# Qwiic_GPS.net
KiCad netlist of a schematic drawn in EAGLE
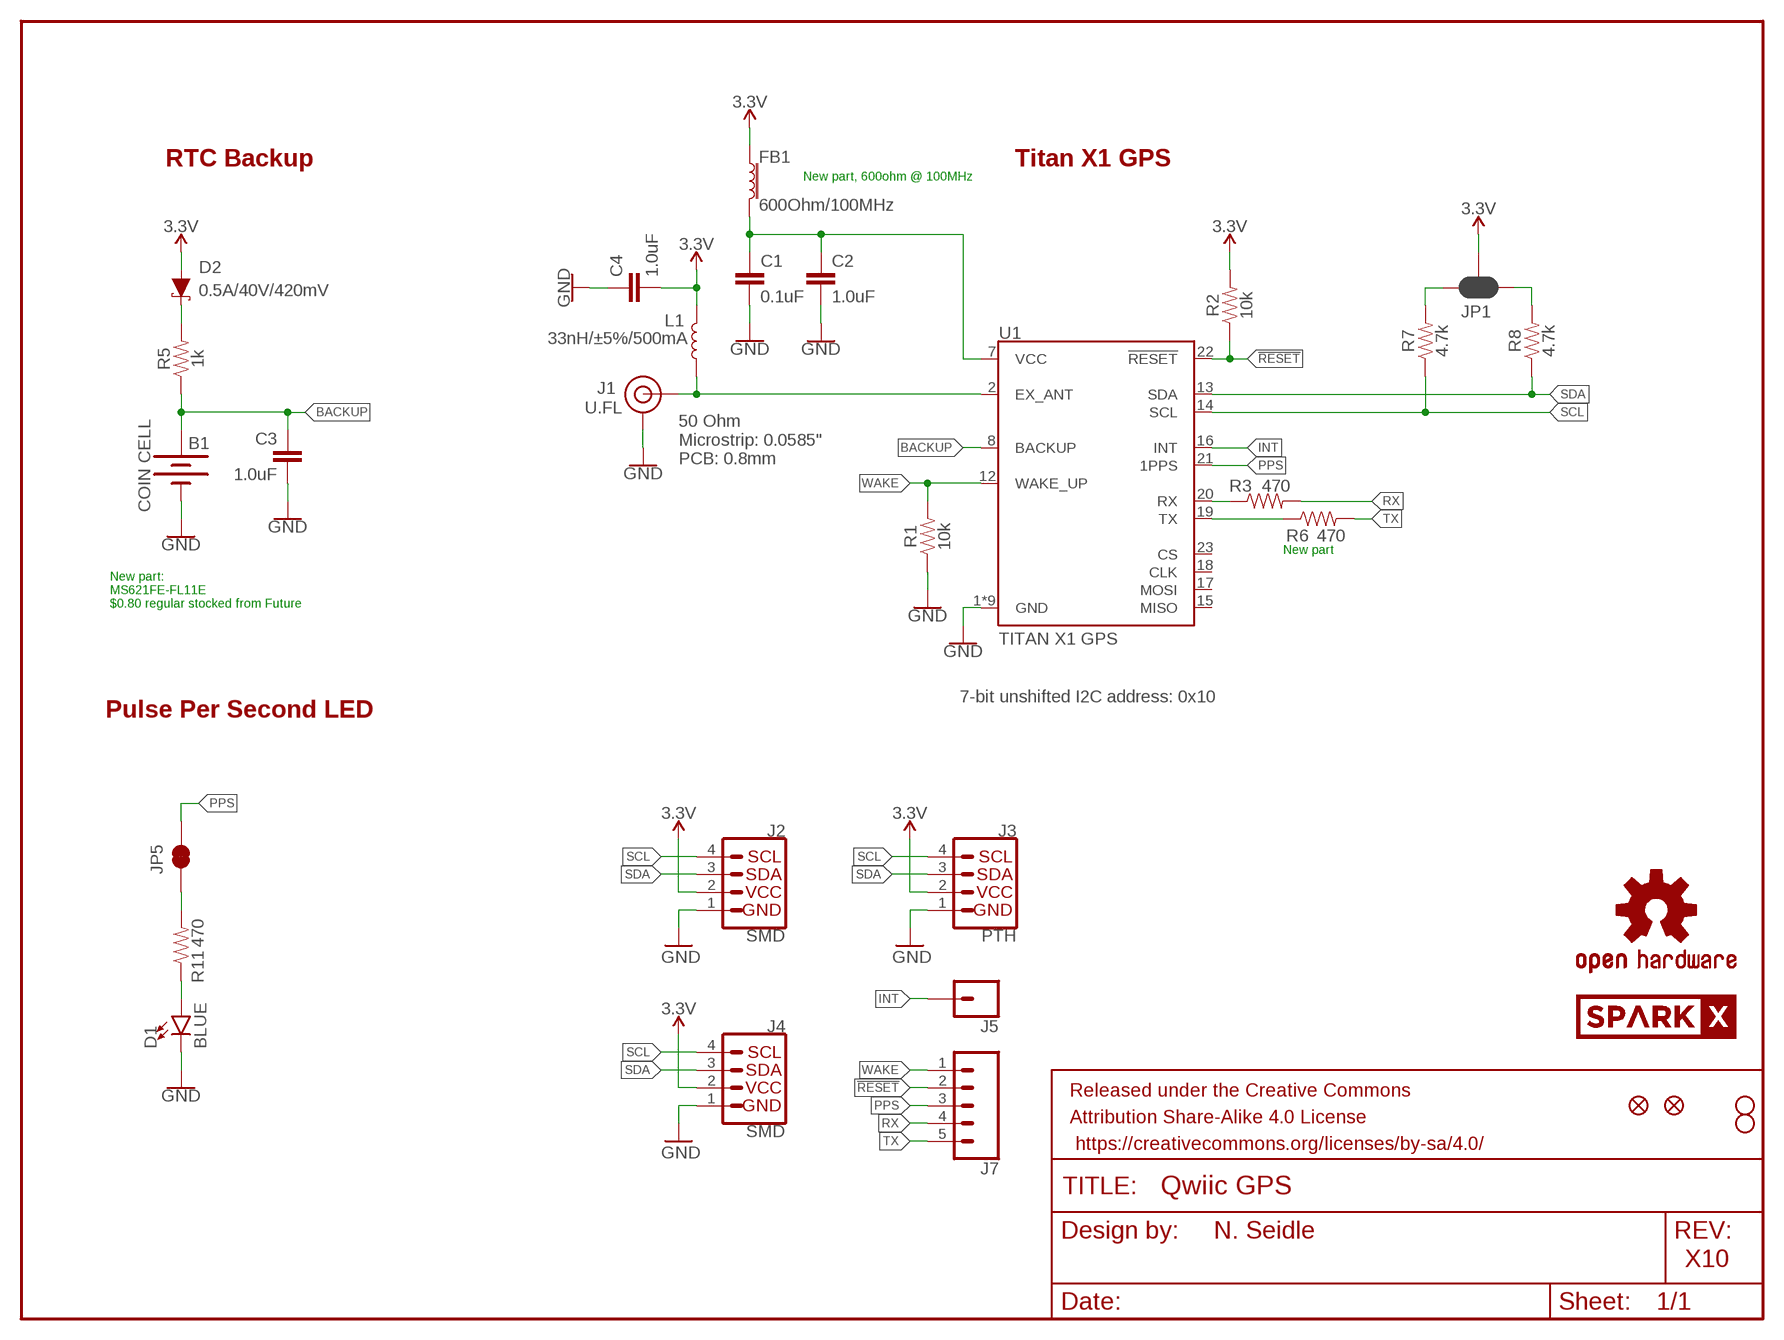
[diagram p0: schematic, sheet 1]

(export (version "E")
  (design (tool "Eeschema 10.0.6"))
  (components
    (comp (ref "B1")
      (value "COIN CELL")
      (footprint "eagle-import:6.8MM_COIN_CELL")
      (libsource (lib "eagle-import") (part "6.8MM_COIN_CELL"))
    )
    (comp (ref "C1")
      (value "0.1uF")
      (footprint "eagle-import:0603")
      (libsource (lib "eagle-import") (part "0.1UF-0603-25V-(+80/-20%)"))
    )
    (comp (ref "C2")
      (value "1.0uF")
      (footprint "eagle-import:0603")
      (libsource (lib "eagle-import") (part "1.0UF-0603-16V-10%"))
    )
    (comp (ref "C3")
      (value "1.0uF")
      (footprint "eagle-import:0603")
      (libsource (lib "eagle-import") (part "1.0UF-0603-16V-10%"))
    )
    (comp (ref "C4")
      (value "1.0uF")
      (footprint "eagle-import:0603")
      (libsource (lib "eagle-import") (part "1.0UF-0603-16V-10%"))
    )
    (comp (ref "D1")
      (value "BLUE")
      (footprint "eagle-import:LED-0603")
      (libsource (lib "eagle-import") (part "LED-BLUE0603"))
    )
    (comp (ref "D2")
      (value "0.5A/40V/420mV")
      (footprint "eagle-import:SOD-323")
      (libsource (lib "eagle-import") (part "DIODE-SCHOTTKY-PMEG4005EJ"))
    )
    (comp (ref "FB1")
      (value "600Ohm/100MHz")
      (footprint "eagle-import:0603")
      (libsource (lib "eagle-import") (part "FERRITE_BEAD-0603"))
    )
    (comp (ref "FRAME1")
      (value "FRAME-LETTER")
      (footprint "eagle-import:CREATIVE_COMMONS")
      (libsource (lib "eagle-import") (part "FRAME-LETTER"))
    )
    (comp (ref "J1")
      (value "U.FL")
      (footprint "eagle-import:U.FL")
      (libsource (lib "eagle-import") (part "U.FL"))
    )
    (comp (ref "J2")
      (value "SMD")
      (footprint "eagle-import:1X04_1MM_RA")
      (libsource (lib "eagle-import") (part "I2C_STANDARDJS-1MM"))
    )
    (comp (ref "J3")
      (value "PTH")
      (footprint "eagle-import:1X04_NO_SILK")
      (libsource (lib "eagle-import") (part "I2C_STANDARD_NO_SILK"))
    )
    (comp (ref "J4")
      (value "SMD")
      (footprint "eagle-import:1X04_1MM_RA")
      (libsource (lib "eagle-import") (part "I2C_STANDARDJS-1MM"))
    )
    (comp (ref "J5")
      (value "CONN_01PTH_NO_SILK_YES_STOP")
      (footprint "eagle-import:1X01_NO_SILK")
      (libsource (lib "eagle-import") (part "CONN_01PTH_NO_SILK_YES_STOP"))
    )
    (comp (ref "J7")
      (value "CONN_05NO_SILK")
      (footprint "eagle-import:1X05_NO_SILK")
      (libsource (lib "eagle-import") (part "CONN_05NO_SILK"))
    )
    (comp (ref "JP1")
      (value "JUMPER-SMT_3_2-NC_PASTE_SILK")
      (footprint "eagle-import:SMT-JUMPER_3_2-NC_PASTE_SILK")
      (libsource (lib "eagle-import") (part "JUMPER-SMT_3_2-NC_PASTE_SILK"))
    )
    (comp (ref "JP2")
      (value "FIDUCIALUFIDUCIAL")
      (footprint "eagle-import:MICRO-FIDUCIAL")
      (libsource (lib "eagle-import") (part "FIDUCIALUFIDUCIAL"))
    )
    (comp (ref "JP3")
      (value "STAND-OFF")
      (footprint "eagle-import:STAND-OFF")
      (libsource (lib "eagle-import") (part "STAND-OFF"))
    )
    (comp (ref "JP4")
      (value "STAND-OFF")
      (footprint "eagle-import:STAND-OFF")
      (libsource (lib "eagle-import") (part "STAND-OFF"))
    )
    (comp (ref "JP5")
      (value "JUMPER-SMT_2_NC_TRACE_NO-SILK")
      (footprint "eagle-import:SMT-JUMPER_2_NC_TRACE_NO-SILK")
      (libsource (lib "eagle-import") (part "JUMPER-SMT_2_NC_TRACE_NO-SILK"))
    )
    (comp (ref "JP6")
      (value "FIDUCIALUFIDUCIAL")
      (footprint "eagle-import:MICRO-FIDUCIAL")
      (libsource (lib "eagle-import") (part "FIDUCIALUFIDUCIAL"))
    )
    (comp (ref "L1")
      (value "33nH/±5%/500mA")
      (footprint "eagle-import:0603")
      (libsource (lib "eagle-import") (part "INDUCTOR-0603-33NH"))
    )
    (comp (ref "LOGO1")
      (value "OSHW-LOGOMINI")
      (footprint "eagle-import:OSHW-LOGO-MINI")
      (libsource (lib "eagle-import") (part "OSHW-LOGOMINI"))
    )
    (comp (ref "R1")
      (value "10k")
      (footprint "eagle-import:0603")
      (libsource (lib "eagle-import") (part "10KOHM-0603-1/10W-1%"))
    )
    (comp (ref "R2")
      (value "10k")
      (footprint "eagle-import:0603")
      (libsource (lib "eagle-import") (part "10KOHM-0603-1/10W-1%"))
    )
    (comp (ref "R3")
      (value "470")
      (footprint "eagle-import:0603")
      (libsource (lib "eagle-import") (part "470OHM-0603-1/10W-1%"))
    )
    (comp (ref "R5")
      (value "1k")
      (footprint "eagle-import:0603")
      (libsource (lib "eagle-import") (part "1KOHM-0603-1/10W-1%"))
    )
    (comp (ref "R6")
      (value "470")
      (footprint "eagle-import:0603")
      (libsource (lib "eagle-import") (part "470OHM-0603-1/10W-1%"))
    )
    (comp (ref "R7")
      (value "4.7k")
      (footprint "eagle-import:0603")
      (libsource (lib "eagle-import") (part "4.7KOHM-0603-1/10W-1%"))
    )
    (comp (ref "R8")
      (value "4.7k")
      (footprint "eagle-import:0603")
      (libsource (lib "eagle-import") (part "4.7KOHM-0603-1/10W-1%"))
    )
    (comp (ref "R11")
      (value "470")
      (footprint "eagle-import:0603")
      (libsource (lib "eagle-import") (part "470OHM-0603-1/10W-1%"))
    )
    (comp (ref "U$1")
      (value "SPARKX-LOGO5")
      (footprint "eagle-import:SPARKX-LARGE")
      (libsource (lib "eagle-import") (part "SPARKX-LOGO5"))
    )
    (comp (ref "U1")
      (value "TITAN X1 GPS")
      (footprint "eagle-import:TITAN_X1_GPS")
      (libsource (lib "eagle-import") (part "TITAN_X1_GPS"))
    )
  )
  (nets
    (net (code "1") (name "/~{RESET}") (class "Default")
      (node (ref "J7") (pin "2") (pinfunction "2_2") (pintype "passive"))
      (node (ref "R2") (pin "1") (pinfunction "1_1") (pintype "passive"))
      (node (ref "U1") (pin "22") (pinfunction "~{RESET}_22") (pintype "bidirectional"))
    )
    (net (code "2") (name "3.3V") (class "Default")
      (node (ref "C4") (pin "2") (pinfunction "2_2") (pintype "passive"))
      (node (ref "D2") (pin "A") (pinfunction "A_A") (pintype "passive"))
      (node (ref "FB1") (pin "1") (pinfunction "1_1") (pintype "passive"))
      (node (ref "J2") (pin "2") (pinfunction "VCC_2") (pintype "power_in"))
      (node (ref "J3") (pin "2") (pinfunction "VCC_2") (pintype "power_in"))
      (node (ref "J4") (pin "2") (pinfunction "VCC_2") (pintype "power_in"))
      (node (ref "JP1") (pin "2") (pinfunction "2_2") (pintype "passive"))
      (node (ref "L1") (pin "2") (pinfunction "2_2") (pintype "passive"))
      (node (ref "R2") (pin "2") (pinfunction "2_2") (pintype "passive"))
    )
    (net (code "3") (name "BACKUP") (class "Default")
      (node (ref "B1") (pin "+") (pinfunction "+_+") (pintype "power_in"))
      (node (ref "C3") (pin "1") (pinfunction "1_1") (pintype "passive"))
      (node (ref "R5") (pin "1") (pinfunction "1_1") (pintype "passive"))
      (node (ref "U1") (pin "8") (pinfunction "BACKUP_8") (pintype "bidirectional"))
    )
    (net (code "4") (name "GND") (class "Default")
      (node (ref "B1") (pin "-") (pinfunction "-_-") (pintype "power_in"))
      (node (ref "C1") (pin "2") (pinfunction "2_2") (pintype "passive"))
      (node (ref "C2") (pin "2") (pinfunction "2_2") (pintype "passive"))
      (node (ref "C3") (pin "2") (pinfunction "2_2") (pintype "passive"))
      (node (ref "C4") (pin "1") (pinfunction "1_1") (pintype "passive"))
      (node (ref "D1") (pin "C") (pinfunction "C_C") (pintype "passive"))
      (node (ref "J1") (pin "1") (pinfunction "GND_1") (pintype "bidirectional"))
      (node (ref "J1") (pin "2") (pinfunction "GND_2") (pintype "bidirectional"))
      (node (ref "J2") (pin "1") (pinfunction "GND_1") (pintype "power_in"))
      (node (ref "J3") (pin "1") (pinfunction "GND_1") (pintype "power_in"))
      (node (ref "J4") (pin "1") (pinfunction "GND_1") (pintype "power_in"))
      (node (ref "R1") (pin "1") (pinfunction "1_1") (pintype "passive"))
      (node (ref "U1") (pin "1") (pinfunction "GND_1") (pintype "bidirectional"))
      (node (ref "U1") (pin "10") (pinfunction "GND_10") (pintype "bidirectional"))
      (node (ref "U1") (pin "11") (pinfunction "GND_11") (pintype "bidirectional"))
      (node (ref "U1") (pin "24") (pinfunction "GND_24") (pintype "bidirectional"))
      (node (ref "U1") (pin "3") (pinfunction "GND_3") (pintype "bidirectional"))
      (node (ref "U1") (pin "4") (pinfunction "GND_4") (pintype "bidirectional"))
      (node (ref "U1") (pin "5") (pinfunction "GND_5") (pintype "bidirectional"))
      (node (ref "U1") (pin "6") (pinfunction "GND_6") (pintype "bidirectional"))
      (node (ref "U1") (pin "9") (pinfunction "GND_9") (pintype "bidirectional"))
    )
    (net (code "5") (name "INT") (class "Default")
      (node (ref "J5") (pin "1") (pinfunction "1_1") (pintype "passive"))
      (node (ref "U1") (pin "16") (pinfunction "INT_16") (pintype "bidirectional"))
    )
    (net (code "6") (name "Net-(D1-PadA)") (class "Default")
      (node (ref "D1") (pin "A") (pinfunction "A_A") (pintype "passive"))
      (node (ref "R11") (pin "1") (pinfunction "1_1") (pintype "passive"))
    )
    (net (code "7") (name "Net-(D2-PadC)") (class "Default")
      (node (ref "D2") (pin "C") (pinfunction "C_C") (pintype "passive"))
      (node (ref "R5") (pin "2") (pinfunction "2_2") (pintype "passive"))
    )
    (net (code "8") (name "Net-(J1-SIGNAL)") (class "Default")
      (node (ref "J1") (pin "FEED") (pinfunction "SIGNAL_FEED") (pintype "bidirectional"))
      (node (ref "L1") (pin "1") (pinfunction "1_1") (pintype "passive"))
      (node (ref "U1") (pin "2") (pinfunction "EX_ANT_2") (pintype "bidirectional"))
    )
    (net (code "9") (name "Net-(JP1-Pad1)") (class "Default")
      (node (ref "JP1") (pin "1") (pinfunction "1_1") (pintype "passive"))
      (node (ref "R8") (pin "2") (pinfunction "2_2") (pintype "passive"))
    )
    (net (code "10") (name "Net-(JP1-Pad3)") (class "Default")
      (node (ref "JP1") (pin "3") (pinfunction "3_3") (pintype "passive"))
      (node (ref "R7") (pin "2") (pinfunction "2_2") (pintype "passive"))
    )
    (net (code "11") (name "Net-(JP5-Pad1)") (class "Default")
      (node (ref "JP5") (pin "1") (pinfunction "1_1") (pintype "passive"))
      (node (ref "R11") (pin "2") (pinfunction "2_2") (pintype "passive"))
    )
    (net (code "12") (name "Net-(U1-RX)") (class "Default")
      (node (ref "R3") (pin "1") (pinfunction "1_1") (pintype "passive"))
      (node (ref "U1") (pin "20") (pinfunction "RX_20") (pintype "bidirectional"))
    )
    (net (code "13") (name "Net-(U1-TX)") (class "Default")
      (node (ref "R6") (pin "1") (pinfunction "1_1") (pintype "passive"))
      (node (ref "U1") (pin "19") (pinfunction "TX_19") (pintype "bidirectional"))
    )
    (net (code "14") (name "Net-(U1-VCC)") (class "Default")
      (node (ref "C1") (pin "1") (pinfunction "1_1") (pintype "passive"))
      (node (ref "C2") (pin "1") (pinfunction "1_1") (pintype "passive"))
      (node (ref "FB1") (pin "2") (pinfunction "2_2") (pintype "passive"))
      (node (ref "U1") (pin "7") (pinfunction "VCC_7") (pintype "bidirectional"))
    )
    (net (code "15") (name "PPS") (class "Default")
      (node (ref "J7") (pin "3") (pinfunction "3_3") (pintype "passive"))
      (node (ref "JP5") (pin "2") (pinfunction "2_2") (pintype "passive"))
      (node (ref "U1") (pin "21") (pinfunction "1PPS_21") (pintype "bidirectional"))
    )
    (net (code "16") (name "RX") (class "Default")
      (node (ref "J7") (pin "4") (pinfunction "4_4") (pintype "passive"))
      (node (ref "R3") (pin "2") (pinfunction "2_2") (pintype "passive"))
    )
    (net (code "17") (name "SCL") (class "Default")
      (node (ref "J2") (pin "4") (pinfunction "SCL_4") (pintype "passive"))
      (node (ref "J3") (pin "4") (pinfunction "SCL_4") (pintype "passive"))
      (node (ref "J4") (pin "4") (pinfunction "SCL_4") (pintype "passive"))
      (node (ref "R7") (pin "1") (pinfunction "1_1") (pintype "passive"))
      (node (ref "U1") (pin "14") (pinfunction "SCL_14") (pintype "bidirectional"))
    )
    (net (code "18") (name "SDA") (class "Default")
      (node (ref "J2") (pin "3") (pinfunction "SDA_3") (pintype "passive"))
      (node (ref "J3") (pin "3") (pinfunction "SDA_3") (pintype "passive"))
      (node (ref "J4") (pin "3") (pinfunction "SDA_3") (pintype "passive"))
      (node (ref "R8") (pin "1") (pinfunction "1_1") (pintype "passive"))
      (node (ref "U1") (pin "13") (pinfunction "SDA_13") (pintype "bidirectional"))
    )
    (net (code "19") (name "TX") (class "Default")
      (node (ref "J7") (pin "5") (pinfunction "5_5") (pintype "passive"))
      (node (ref "R6") (pin "2") (pinfunction "2_2") (pintype "passive"))
    )
    (net (code "20") (name "WAKE") (class "Default")
      (node (ref "J7") (pin "1") (pinfunction "1_1") (pintype "passive"))
      (node (ref "R1") (pin "2") (pinfunction "2_2") (pintype "passive"))
      (node (ref "U1") (pin "12") (pinfunction "WAKE_UP_12") (pintype "bidirectional"))
    )
    (net (code "21") (name "unconnected-(U1-CLK-Pad18)") (class "Default")
      (node (ref "U1") (pin "18") (pinfunction "CLK_18") (pintype "bidirectional"))
    )
    (net (code "22") (name "unconnected-(U1-CS-Pad23)") (class "Default")
      (node (ref "U1") (pin "23") (pinfunction "CS_23") (pintype "bidirectional"))
    )
    (net (code "23") (name "unconnected-(U1-MISO-Pad15)") (class "Default")
      (node (ref "U1") (pin "15") (pinfunction "MISO_15") (pintype "bidirectional"))
    )
    (net (code "24") (name "unconnected-(U1-MOSI-Pad17)") (class "Default")
      (node (ref "U1") (pin "17") (pinfunction "MOSI_17") (pintype "bidirectional"))
    )
  )
)
